# Sheet.net
KiCad netlist of a schematic drawn in Altium Designer
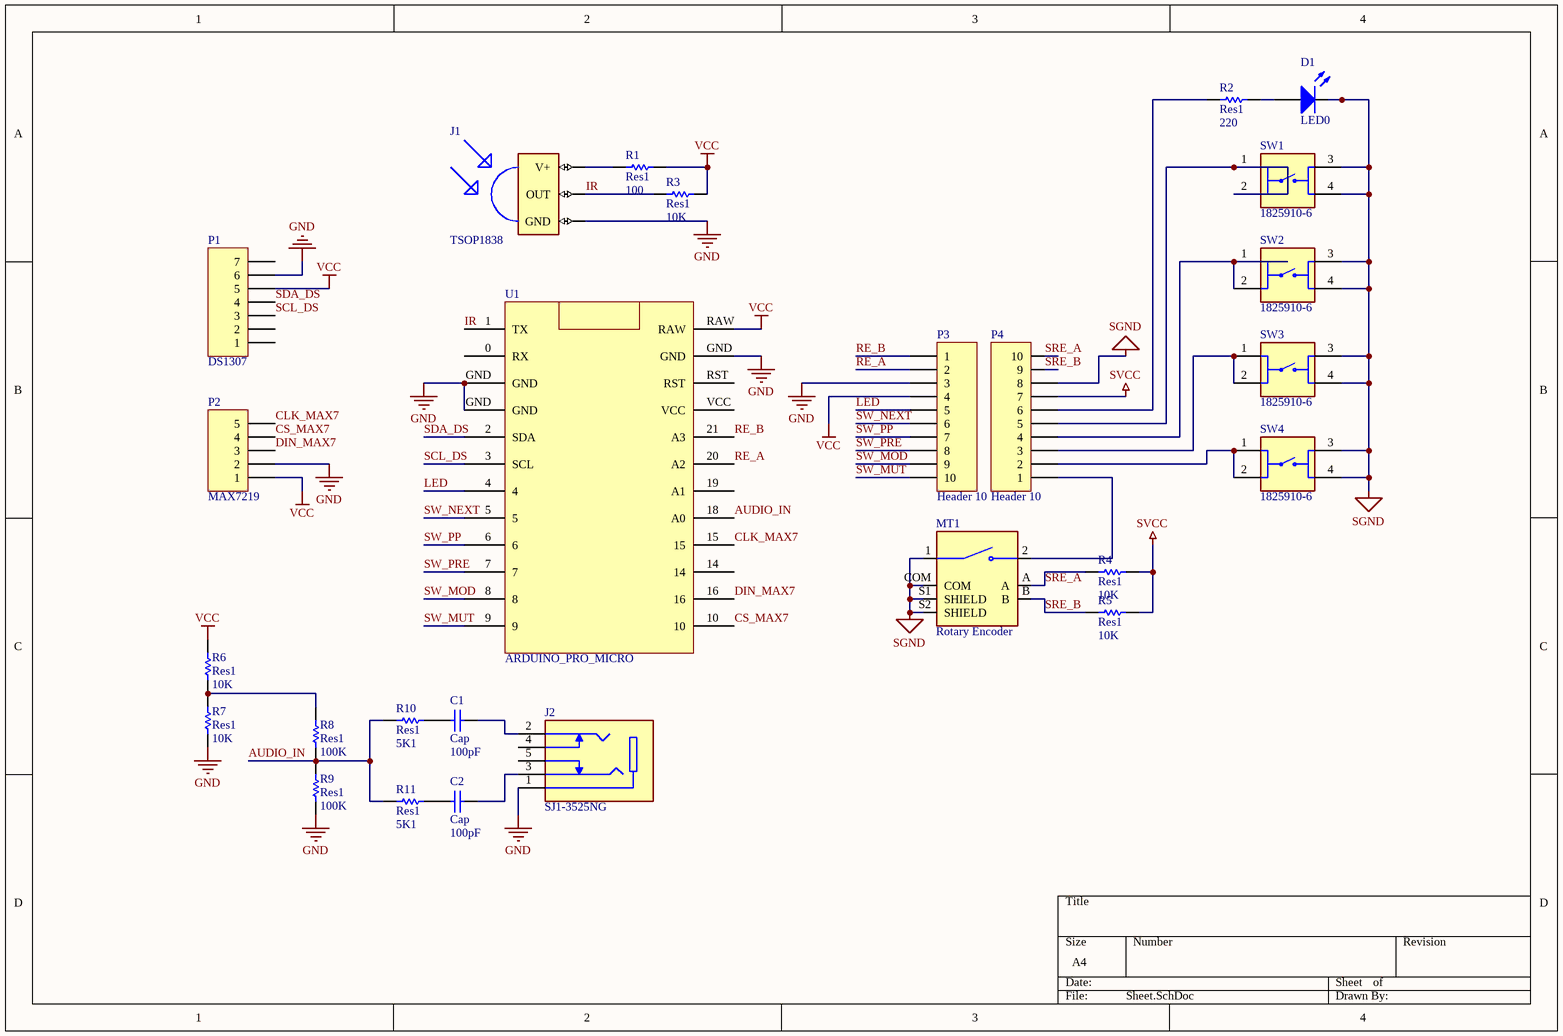
[diagram p0: Sheet.SchDoc]

(export (version "E")
  (design (tool "Eeschema 10.0.6"))
  (components
    (comp (ref "C1")
      (value "Cap")
      (footprint "RAD-0.3")
      (description "Capacitor")
      (fields (field (name "ALTIUM_VALUE") "100pF") (field (name "PUBLISHER") "Altium Limited"))
      (libsource (lib "Miscellaneous Devices") (part "Cap"))
    )
    (comp (ref "C2")
      (value "Cap")
      (footprint "RAD-0.3")
      (description "Capacitor")
      (fields (field (name "ALTIUM_VALUE") "100pF") (field (name "PUBLISHER") "Altium Limited"))
      (libsource (lib "Miscellaneous Devices") (part "Cap"))
    )
    (comp (ref "D1")
      (value "LED0")
      (footprint "LED-0")
      (description "Typical INFRARED GaAs LED")
      (fields (field (name "PUBLISHER") "Altium Limited"))
      (libsource (lib "Miscellaneous Devices") (part "LED0"))
    )
    (comp (ref "J1")
      (value "TSOP1838")
      (footprint "TSOP18XX:TSOP18XX")
      (description "IR Receiver and Demodulator")
      (libsource (lib "TSOP1838") (part "TSOP1838"))
    )
    (comp (ref "J2")
      (value "SJ1-3525NG")
      (footprint "CUI_SJ1-3525NG")
      (description "3.5 mm Right-Angle Stereo Jack, 5 Pin PCB Mount, Isolated Ground")
      (libsource (lib "SJ1-3525NG") (part "SJ1-3525NG"))
    )
    (comp (ref "MT1")
      (value "Rotary Encoder")
      (footprint "RotaryEncoder:XDCR_PEC11R-4215F-S0024")
      (description "Incremental Encoder, 12 Mm, Contact Rating 10 Ma - 5 Vdc")
      (fields (field (name "MP") "PEC11R-4215F-S0024"))
      (libsource (lib "RotaryEncoder") (part "PEC11R-4215F-S0024"))
    )
    (comp (ref "P1")
      (value "DS1307")
      (footprint "HDR1X7")
      (description "Header, 7-Pin")
      (fields (field (name "PUBLISHER") "Altium Limited"))
      (libsource (lib "Miscellaneous Connectors") (part "Header 7"))
    )
    (comp (ref "P2")
      (value "MAX7219")
      (footprint "HDR1X5")
      (description "Header, 5-Pin")
      (fields (field (name "PUBLISHER") "Altium Limited"))
      (libsource (lib "Miscellaneous Connectors") (part "Header 5"))
    )
    (comp (ref "P3")
      (value "Header 10")
      (footprint "HDR1X10")
      (description "Header, 10-Pin")
      (fields (field (name "PUBLISHER") "Altium Limited"))
      (libsource (lib "") (part "Header 10_1"))
    )
    (comp (ref "P4")
      (value "Header 10")
      (footprint "HDR1X10")
      (description "Header, 10-Pin")
      (fields (field (name "PUBLISHER") "Altium Limited"))
      (libsource (lib "Miscellaneous Connectors") (part "Header 10"))
    )
    (comp (ref "R1")
      (value "Res1")
      (footprint "RESC3116X65N")
      (description "Resistor")
      (fields (field (name "ALTIUM_VALUE") "100") (field (name "PUBLISHER") "Altium Limited"))
      (libsource (lib "Miscellaneous Devices") (part "Res1"))
    )
    (comp (ref "R2")
      (value "Res1")
      (footprint "RESC3116X65N")
      (description "Resistor")
      (fields (field (name "ALTIUM_VALUE") "220") (field (name "PUBLISHER") "Altium Limited"))
      (libsource (lib "Miscellaneous Devices") (part "Res1"))
    )
    (comp (ref "R3")
      (value "Res1")
      (footprint "RESC3116X65N")
      (description "Resistor")
      (fields (field (name "ALTIUM_VALUE") "10K") (field (name "PUBLISHER") "Altium Limited"))
      (libsource (lib "Miscellaneous Devices") (part "Res1"))
    )
    (comp (ref "R4")
      (value "Res1")
      (footprint "RESC3116X65N")
      (description "Resistor")
      (fields (field (name "ALTIUM_VALUE") "10K") (field (name "PUBLISHER") "Altium Limited"))
      (libsource (lib "Miscellaneous Devices") (part "Res1"))
    )
    (comp (ref "R5")
      (value "Res1")
      (footprint "RESC3116X65N")
      (description "Resistor")
      (fields (field (name "ALTIUM_VALUE") "10K") (field (name "PUBLISHER") "Altium Limited"))
      (libsource (lib "Miscellaneous Devices") (part "Res1"))
    )
    (comp (ref "R6")
      (value "Res1")
      (footprint "RESC3116X65N")
      (description "Resistor")
      (fields (field (name "ALTIUM_VALUE") "10K") (field (name "PUBLISHER") "Altium Limited"))
      (libsource (lib "Miscellaneous Devices") (part "Res1"))
    )
    (comp (ref "R7")
      (value "Res1")
      (footprint "RESC3116X65N")
      (description "Resistor")
      (fields (field (name "ALTIUM_VALUE") "10K") (field (name "PUBLISHER") "Altium Limited"))
      (libsource (lib "Miscellaneous Devices") (part "Res1"))
    )
    (comp (ref "R8")
      (value "Res1")
      (footprint "RESC3116X65N")
      (description "Resistor")
      (fields (field (name "ALTIUM_VALUE") "100K") (field (name "PUBLISHER") "Altium Limited"))
      (libsource (lib "Miscellaneous Devices") (part "Res1"))
    )
    (comp (ref "R9")
      (value "Res1")
      (footprint "RESC3116X65N")
      (description "Resistor")
      (fields (field (name "ALTIUM_VALUE") "100K") (field (name "PUBLISHER") "Altium Limited"))
      (libsource (lib "Miscellaneous Devices") (part "Res1"))
    )
    (comp (ref "R10")
      (value "Res1")
      (footprint "RESC3116X65N")
      (description "Resistor")
      (fields (field (name "ALTIUM_VALUE") "5K1") (field (name "PUBLISHER") "Altium Limited"))
      (libsource (lib "Miscellaneous Devices") (part "Res1"))
    )
    (comp (ref "R11")
      (value "Res1")
      (footprint "RESC3116X65N")
      (description "Resistor")
      (fields (field (name "ALTIUM_VALUE") "5K1") (field (name "PUBLISHER") "Altium Limited"))
      (libsource (lib "Miscellaneous Devices") (part "Res1"))
    )
    (comp (ref "SW1")
      (value "1825910-6")
      (footprint "SW_1825910-6-4")
      (description "Switch Push Button OFF (ON) SPST Round Button 0.05A 24VDC Momentary Contact PC Pins Thru-Hole")
      (fields (field (name "MF") "TE Connectivity") (field (name "DIGI-KEY_PART_NUMBER") "450-1650-ND"))
      (libsource (lib "1825910-6") (part "1825910-6"))
    )
    (comp (ref "SW2")
      (value "1825910-6")
      (footprint "SW_1825910-6-4")
      (description "Switch Push Button OFF (ON) SPST Round Button 0.05A 24VDC Momentary Contact PC Pins Thru-Hole")
      (fields (field (name "MF") "TE Connectivity") (field (name "DIGI-KEY_PART_NUMBER") "450-1650-ND"))
      (libsource (lib "1825910-6") (part "1825910-6"))
    )
    (comp (ref "SW3")
      (value "1825910-6")
      (footprint "SW_1825910-6-4")
      (description "Switch Push Button OFF (ON) SPST Round Button 0.05A 24VDC Momentary Contact PC Pins Thru-Hole")
      (fields (field (name "MF") "TE Connectivity") (field (name "DIGI-KEY_PART_NUMBER") "450-1650-ND"))
      (libsource (lib "1825910-6") (part "1825910-6"))
    )
    (comp (ref "SW4")
      (value "1825910-6")
      (footprint "SW_1825910-6-4")
      (description "Switch Push Button OFF (ON) SPST Round Button 0.05A 24VDC Momentary Contact PC Pins Thru-Hole")
      (fields (field (name "MF") "TE Connectivity") (field (name "DIGI-KEY_PART_NUMBER") "450-1650-ND"))
      (libsource (lib "1825910-6") (part "1825910-6"))
    )
    (comp (ref "U1")
      (value "ARDUINO_PRO_MICRO")
      (footprint "MODULE_ARDUINO_PRO_MINI")
      (fields (field (name "MF") "Arduino") (field (name "MP") "Arduino Pro Mini"))
      (libsource (lib "ARDUINO_PRO_MICRO") (part "ARDUINO_PRO_MICRO"))
    )
  )
  (nets
    (net (code "1") (name "/AUDIO_IN") (class "Default")
      (node (ref "R10") (pin "1") (pinfunction "1_1") (pintype "passive"))
      (node (ref "R11") (pin "1") (pinfunction "1_1") (pintype "passive"))
      (node (ref "R8") (pin "2") (pinfunction "2_2") (pintype "passive"))
      (node (ref "R9") (pin "2") (pinfunction "2_2") (pintype "passive"))
      (node (ref "U1") (pin "18") (pinfunction "A0_18") (pintype "passive"))
    )
    (net (code "2") (name "/CLK_MAX7") (class "Default")
      (node (ref "P2") (pin "5") (pinfunction "5_5") (pintype "passive"))
      (node (ref "U1") (pin "15") (pinfunction "15_15") (pintype "passive"))
    )
    (net (code "3") (name "/CS_MAX7") (class "Default")
      (node (ref "P2") (pin "4") (pinfunction "4_4") (pintype "passive"))
      (node (ref "U1") (pin "10") (pinfunction "10_10") (pintype "passive"))
    )
    (net (code "4") (name "/DIN_MAX7") (class "Default")
      (node (ref "P2") (pin "3") (pinfunction "3_3") (pintype "passive"))
      (node (ref "U1") (pin "16") (pinfunction "16_16") (pintype "passive"))
    )
    (net (code "5") (name "/IR") (class "Default")
      (node (ref "J1") (pin "OUT") (pinfunction "OUT_OUT") (pintype "bidirectional"))
      (node (ref "R3") (pin "1") (pinfunction "1_1") (pintype "passive"))
      (node (ref "U1") (pin "1") (pinfunction "TX_1") (pintype "passive"))
    )
    (net (code "6") (name "/LED") (class "Default")
      (node (ref "P3") (pin "5") (pinfunction "5_5") (pintype "passive"))
      (node (ref "U1") (pin "4") (pinfunction "4_4") (pintype "passive"))
    )
    (net (code "7") (name "/RE_A") (class "Default")
      (node (ref "P3") (pin "2") (pinfunction "2_2") (pintype "passive"))
      (node (ref "U1") (pin "20") (pinfunction "A2_20") (pintype "passive"))
    )
    (net (code "8") (name "/RE_B") (class "Default")
      (node (ref "P3") (pin "1") (pinfunction "1_1") (pintype "passive"))
      (node (ref "U1") (pin "21") (pinfunction "A3_21") (pintype "passive"))
    )
    (net (code "9") (name "/SCL_DS") (class "Default")
      (node (ref "P1") (pin "3") (pinfunction "3_3") (pintype "passive"))
      (node (ref "U1") (pin "3") (pinfunction "SCL_3") (pintype "passive"))
    )
    (net (code "10") (name "/SDA_DS") (class "Default")
      (node (ref "P1") (pin "4") (pinfunction "4_4") (pintype "passive"))
      (node (ref "U1") (pin "2") (pinfunction "SDA_2") (pintype "passive"))
    )
    (net (code "11") (name "/SRE_A") (class "Default")
      (node (ref "MT1") (pin "A") (pinfunction "A_A") (pintype "passive"))
      (node (ref "P4") (pin "10") (pinfunction "10_10") (pintype "passive"))
      (node (ref "R4") (pin "1") (pinfunction "1_1") (pintype "passive"))
    )
    (net (code "12") (name "/SRE_B") (class "Default")
      (node (ref "MT1") (pin "B") (pinfunction "B_B") (pintype "passive"))
      (node (ref "P4") (pin "9") (pinfunction "9_9") (pintype "passive"))
      (node (ref "R5") (pin "1") (pinfunction "1_1") (pintype "passive"))
    )
    (net (code "13") (name "/SW_MOD") (class "Default")
      (node (ref "P3") (pin "9") (pinfunction "9_9") (pintype "passive"))
      (node (ref "U1") (pin "8") (pinfunction "8_8") (pintype "passive"))
    )
    (net (code "14") (name "/SW_MUT") (class "Default")
      (node (ref "P3") (pin "10") (pinfunction "10_10") (pintype "passive"))
      (node (ref "U1") (pin "9") (pinfunction "9_9") (pintype "passive"))
    )
    (net (code "15") (name "/SW_NEXT") (class "Default")
      (node (ref "P3") (pin "6") (pinfunction "6_6") (pintype "passive"))
      (node (ref "U1") (pin "5") (pinfunction "5_5") (pintype "passive"))
    )
    (net (code "16") (name "/SW_PP") (class "Default")
      (node (ref "P3") (pin "7") (pinfunction "7_7") (pintype "passive"))
      (node (ref "U1") (pin "6") (pinfunction "6_6") (pintype "passive"))
    )
    (net (code "17") (name "/SW_PRE") (class "Default")
      (node (ref "P3") (pin "8") (pinfunction "8_8") (pintype "passive"))
      (node (ref "U1") (pin "7") (pinfunction "7_7") (pintype "passive"))
    )
    (net (code "18") (name "GND") (class "Default")
      (node (ref "J1") (pin "GND") (pinfunction "GND_GND") (pintype "bidirectional"))
      (node (ref "J2") (pin "1") (pinfunction "1_1") (pintype "passive"))
      (node (ref "P1") (pin "6") (pinfunction "6_6") (pintype "passive"))
      (node (ref "P2") (pin "2") (pinfunction "2_2") (pintype "passive"))
      (node (ref "P3") (pin "3") (pinfunction "3_3") (pintype "passive"))
      (node (ref "R7") (pin "1") (pinfunction "1_1") (pintype "passive"))
      (node (ref "R9") (pin "1") (pinfunction "1_1") (pintype "passive"))
      (node (ref "U1") (pin "GND") (pinfunction "GND_GND") (pintype "passive"))
    )
    (net (code "19") (name "Net-(C1-Pad1)") (class "Default")
      (node (ref "C1") (pin "1") (pinfunction "1_1") (pintype "passive"))
      (node (ref "R10") (pin "2") (pinfunction "2_2") (pintype "passive"))
    )
    (net (code "20") (name "Net-(C1-Pad2)") (class "Default")
      (node (ref "C1") (pin "2") (pinfunction "2_2") (pintype "passive"))
      (node (ref "J2") (pin "2") (pinfunction "2_2") (pintype "passive"))
    )
    (net (code "21") (name "Net-(C2-Pad1)") (class "Default")
      (node (ref "C2") (pin "1") (pinfunction "1_1") (pintype "passive"))
      (node (ref "R11") (pin "2") (pinfunction "2_2") (pintype "passive"))
    )
    (net (code "22") (name "Net-(C2-Pad2)") (class "Default")
      (node (ref "C2") (pin "2") (pinfunction "2_2") (pintype "passive"))
      (node (ref "J2") (pin "3") (pinfunction "3_3") (pintype "passive"))
    )
    (net (code "23") (name "Net-(D1-A)") (class "Default")
      (node (ref "D1") (pin "1") (pinfunction "A_1") (pintype "passive"))
      (node (ref "R2") (pin "2") (pinfunction "2_2") (pintype "passive"))
    )
    (net (code "24") (name "Net-(J1-V+)") (class "Default")
      (node (ref "J1") (pin "VCC") (pinfunction "V+_VCC") (pintype "bidirectional"))
      (node (ref "R1") (pin "1") (pinfunction "1_1") (pintype "passive"))
    )
    (net (code "25") (name "Net-(MT1-Pad2)") (class "Default")
      (node (ref "MT1") (pin "2") (pinfunction "2_2") (pintype "passive"))
      (node (ref "P4") (pin "1") (pinfunction "1_1") (pintype "passive"))
    )
    (net (code "26") (name "Net-(P4-Pad2)") (class "Default")
      (node (ref "P4") (pin "2") (pinfunction "2_2") (pintype "passive"))
      (node (ref "SW4") (pin "1") (pinfunction "1_1") (pintype "passive"))
      (node (ref "SW4") (pin "2") (pinfunction "2_2") (pintype "passive"))
    )
    (net (code "27") (name "Net-(P4-Pad3)") (class "Default")
      (node (ref "P4") (pin "3") (pinfunction "3_3") (pintype "passive"))
      (node (ref "SW3") (pin "1") (pinfunction "1_1") (pintype "passive"))
      (node (ref "SW3") (pin "2") (pinfunction "2_2") (pintype "passive"))
    )
    (net (code "28") (name "Net-(P4-Pad4)") (class "Default")
      (node (ref "P4") (pin "4") (pinfunction "4_4") (pintype "passive"))
      (node (ref "SW2") (pin "1") (pinfunction "1_1") (pintype "passive"))
      (node (ref "SW2") (pin "2") (pinfunction "2_2") (pintype "passive"))
    )
    (net (code "29") (name "Net-(P4-Pad5)") (class "Default")
      (node (ref "P4") (pin "5") (pinfunction "5_5") (pintype "passive"))
      (node (ref "SW1") (pin "1") (pinfunction "1_1") (pintype "passive"))
      (node (ref "SW1") (pin "2") (pinfunction "2_2") (pintype "passive"))
    )
    (net (code "30") (name "Net-(P4-Pad6)") (class "Default")
      (node (ref "P4") (pin "6") (pinfunction "6_6") (pintype "passive"))
      (node (ref "R2") (pin "1") (pinfunction "1_1") (pintype "passive"))
    )
    (net (code "31") (name "Net-(R6-Pad1)") (class "Default")
      (node (ref "R6") (pin "1") (pinfunction "1_1") (pintype "passive"))
      (node (ref "R7") (pin "2") (pinfunction "2_2") (pintype "passive"))
      (node (ref "R8") (pin "1") (pinfunction "1_1") (pintype "passive"))
    )
    (net (code "32") (name "SGND") (class "Default")
      (node (ref "D1") (pin "2") (pinfunction "K_2") (pintype "passive"))
      (node (ref "MT1") (pin "1") (pinfunction "1_1") (pintype "passive"))
      (node (ref "MT1") (pin "COM") (pinfunction "COM_COM") (pintype "passive"))
      (node (ref "MT1") (pin "S1") (pinfunction "SHIELD_S1") (pintype "passive"))
      (node (ref "MT1") (pin "S2") (pinfunction "SHIELD_S2") (pintype "passive"))
      (node (ref "P4") (pin "8") (pinfunction "8_8") (pintype "passive"))
      (node (ref "SW1") (pin "3") (pinfunction "3_3") (pintype "passive"))
      (node (ref "SW1") (pin "4") (pinfunction "4_4") (pintype "passive"))
      (node (ref "SW2") (pin "3") (pinfunction "3_3") (pintype "passive"))
      (node (ref "SW2") (pin "4") (pinfunction "4_4") (pintype "passive"))
      (node (ref "SW3") (pin "3") (pinfunction "3_3") (pintype "passive"))
      (node (ref "SW3") (pin "4") (pinfunction "4_4") (pintype "passive"))
      (node (ref "SW4") (pin "3") (pinfunction "3_3") (pintype "passive"))
      (node (ref "SW4") (pin "4") (pinfunction "4_4") (pintype "passive"))
    )
    (net (code "33") (name "SVCC") (class "Default")
      (node (ref "P4") (pin "7") (pinfunction "7_7") (pintype "passive"))
      (node (ref "R4") (pin "2") (pinfunction "2_2") (pintype "passive"))
      (node (ref "R5") (pin "2") (pinfunction "2_2") (pintype "passive"))
    )
    (net (code "34") (name "VCC") (class "Default")
      (node (ref "P1") (pin "5") (pinfunction "5_5") (pintype "passive"))
      (node (ref "P2") (pin "1") (pinfunction "1_1") (pintype "passive"))
      (node (ref "P3") (pin "4") (pinfunction "4_4") (pintype "passive"))
      (node (ref "R1") (pin "2") (pinfunction "2_2") (pintype "passive"))
      (node (ref "R3") (pin "2") (pinfunction "2_2") (pintype "passive"))
      (node (ref "R6") (pin "2") (pinfunction "2_2") (pintype "passive"))
      (node (ref "U1") (pin "RAW") (pinfunction "RAW_RAW") (pintype "passive"))
    )
    (net (code "35") (name "unconnected-(J2-Pad4)") (class "Default")
      (node (ref "J2") (pin "4") (pinfunction "4_4") (pintype "passive"))
    )
    (net (code "36") (name "unconnected-(J2-Pad5)") (class "Default")
      (node (ref "J2") (pin "5") (pinfunction "5_5") (pintype "passive"))
    )
    (net (code "37") (name "unconnected-(P1-Pad1)") (class "Default")
      (node (ref "P1") (pin "1") (pinfunction "1_1") (pintype "passive"))
    )
    (net (code "38") (name "unconnected-(P1-Pad2)") (class "Default")
      (node (ref "P1") (pin "2") (pinfunction "2_2") (pintype "passive"))
    )
    (net (code "39") (name "unconnected-(P1-Pad7)") (class "Default")
      (node (ref "P1") (pin "7") (pinfunction "7_7") (pintype "passive"))
    )
    (net (code "40") (name "unconnected-(U1-A1-Pad19)") (class "Default")
      (node (ref "U1") (pin "19") (pinfunction "A1_19") (pintype "passive"))
    )
    (net (code "41") (name "unconnected-(U1-Pad14)") (class "Default")
      (node (ref "U1") (pin "14") (pinfunction "14_14") (pintype "passive"))
    )
    (net (code "42") (name "unconnected-(U1-PadRST)") (class "Default")
      (node (ref "U1") (pin "RST") (pinfunction "RST_RST") (pintype "passive"))
    )
    (net (code "43") (name "unconnected-(U1-PadVCC)") (class "Default")
      (node (ref "U1") (pin "VCC") (pinfunction "VCC_VCC") (pintype "passive"))
    )
    (net (code "44") (name "unconnected-(U1-RX-Pad0)") (class "Default")
      (node (ref "U1") (pin "0") (pinfunction "RX_0") (pintype "passive"))
    )
  )
)
